# composite_router_draft_1.net
KiCad netlist of a schematic drawn in EAGLE
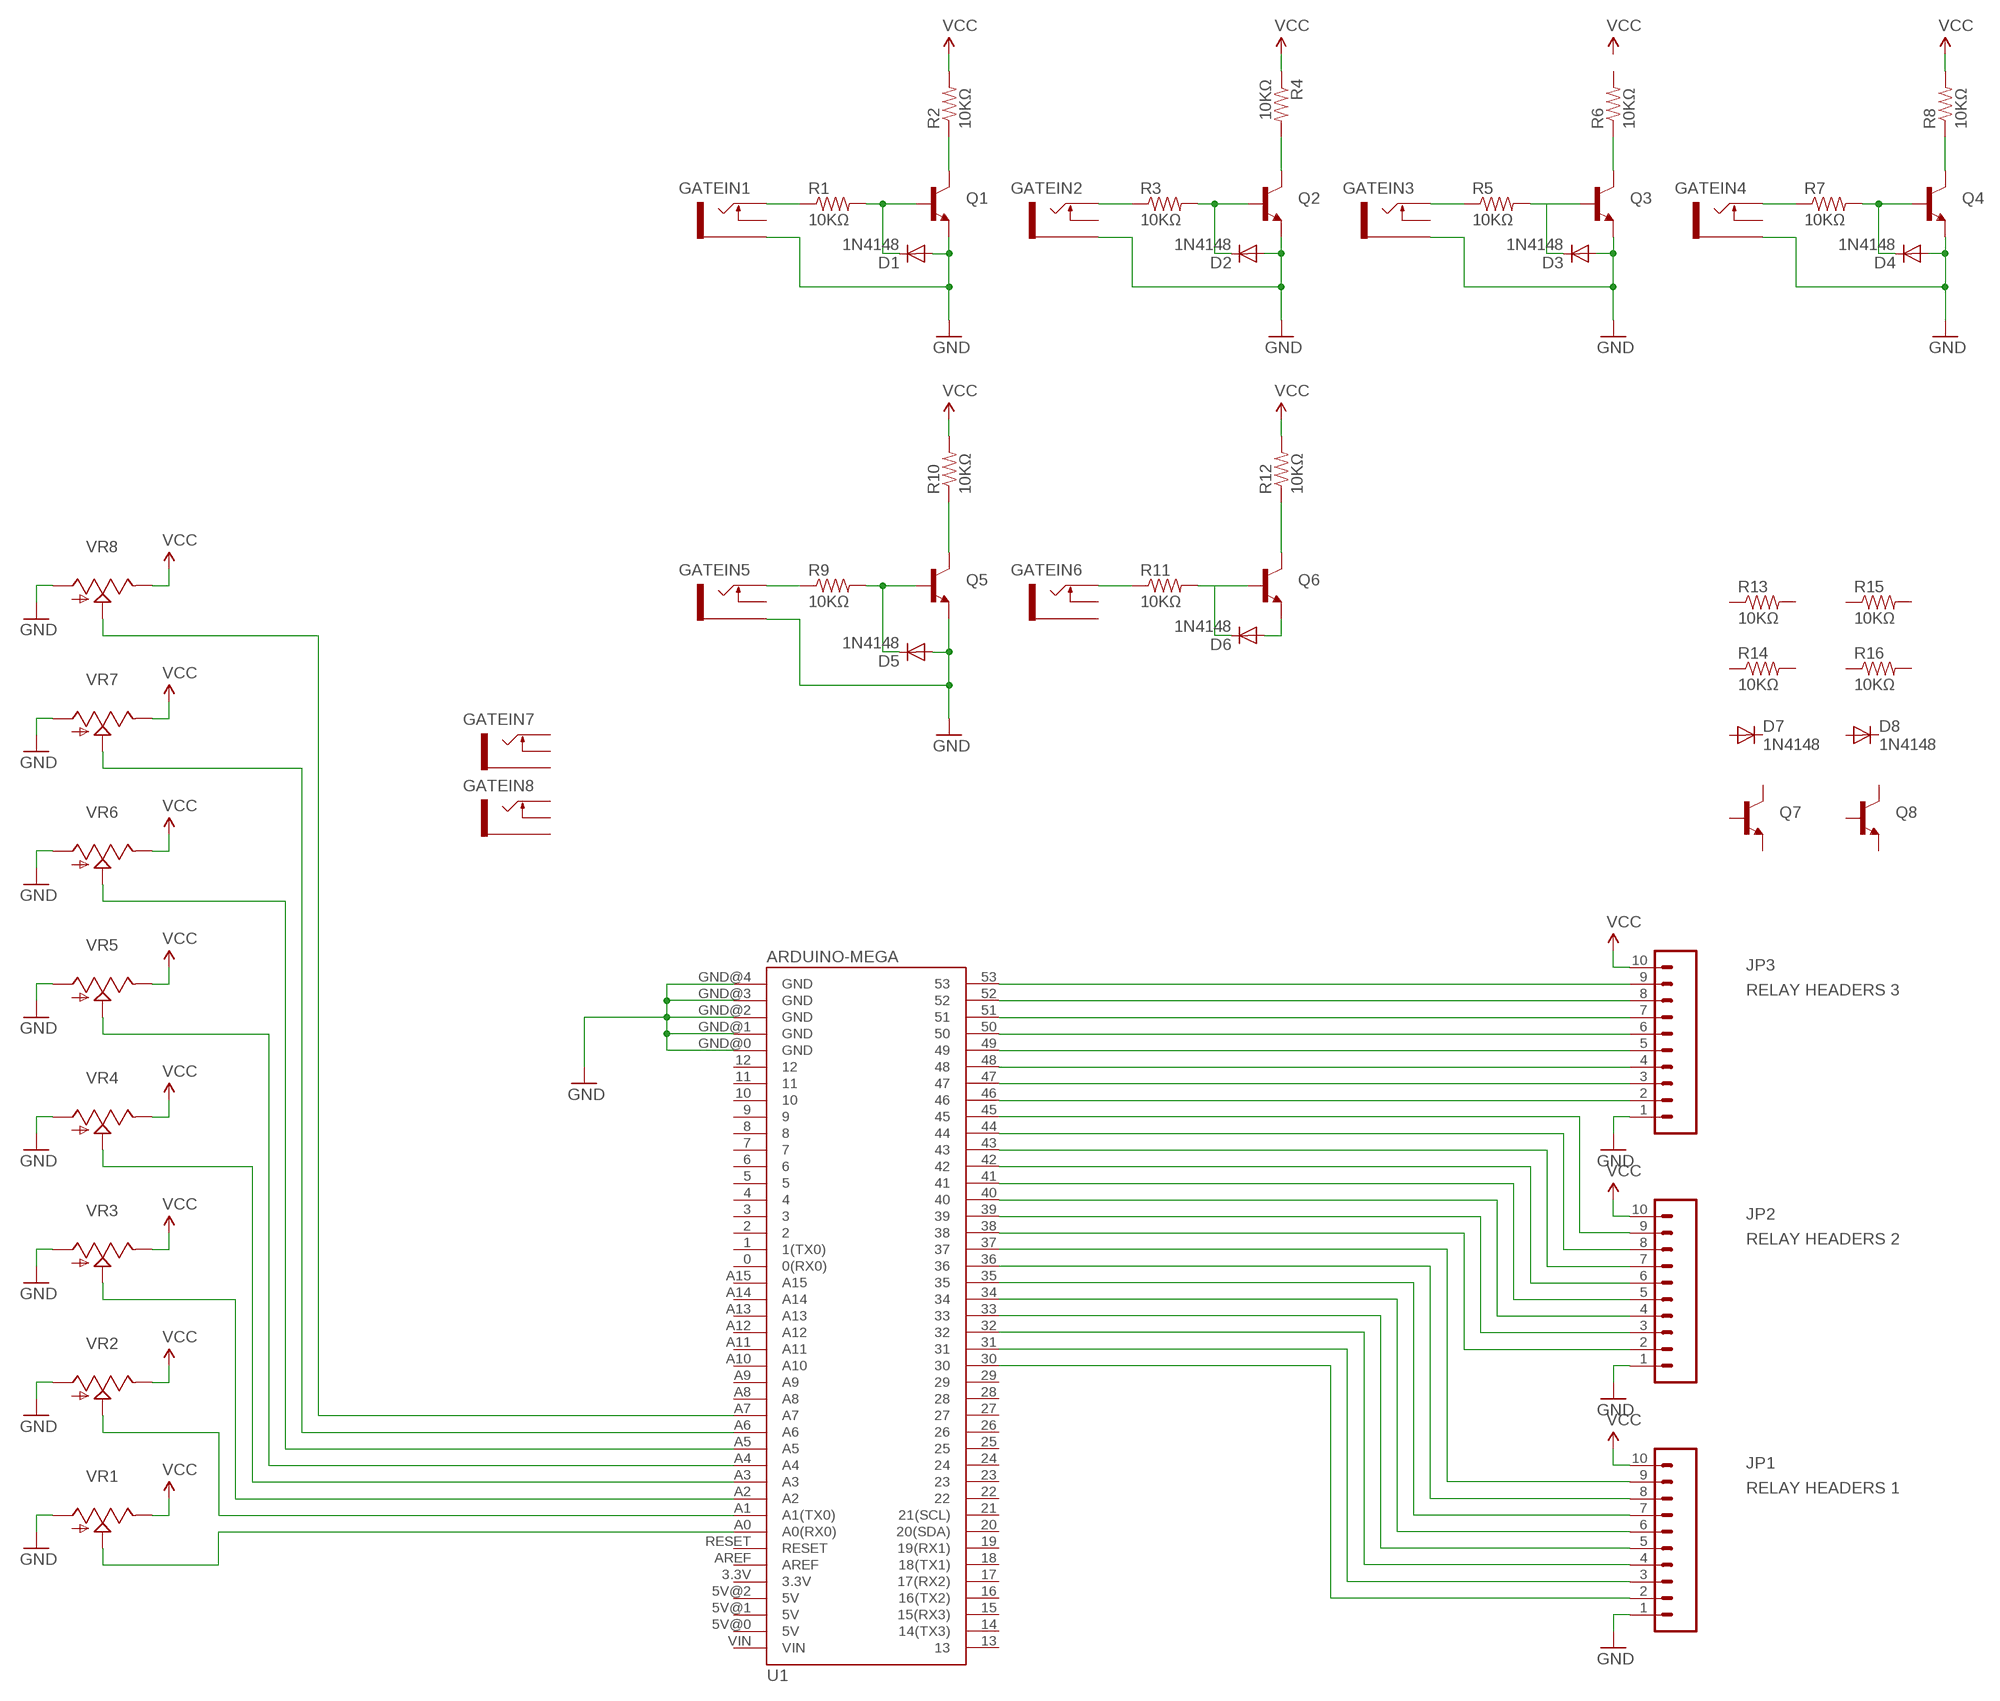
[diagram p0: schematic, sheet 1]

(export (version "E")
  (design (tool "Eeschema 10.0.6"))
  (components
    (comp (ref "D1")
      (value "1N4148")
      (footprint "eagle-import:DO35-7")
      (libsource (lib "eagle-import") (part "1N4148DO35-7"))
    )
    (comp (ref "D2")
      (value "1N4148")
      (footprint "eagle-import:DO35-7")
      (libsource (lib "eagle-import") (part "1N4148DO35-7"))
    )
    (comp (ref "D3")
      (value "1N4148")
      (footprint "eagle-import:DO35-7")
      (libsource (lib "eagle-import") (part "1N4148DO35-7"))
    )
    (comp (ref "D4")
      (value "1N4148")
      (footprint "eagle-import:DO35-7")
      (libsource (lib "eagle-import") (part "1N4148DO35-7"))
    )
    (comp (ref "D5")
      (value "1N4148")
      (footprint "eagle-import:DO35-7")
      (libsource (lib "eagle-import") (part "1N4148DO35-7"))
    )
    (comp (ref "D6")
      (value "1N4148")
      (footprint "eagle-import:DO35-7")
      (libsource (lib "eagle-import") (part "1N4148DO35-7"))
    )
    (comp (ref "D7")
      (value "1N4148")
      (footprint "eagle-import:DO35-7")
      (libsource (lib "eagle-import") (part "1N4148DO35-7"))
    )
    (comp (ref "D8")
      (value "1N4148")
      (footprint "eagle-import:DO35-7")
      (libsource (lib "eagle-import") (part "1N4148DO35-7"))
    )
    (comp (ref "GATEIN1")
      (value "THONKICONNNEW")
      (footprint "eagle-import:WQP-PJ301M-12_JACK")
      (libsource (lib "eagle-import") (part "THONKICONNNEW"))
    )
    (comp (ref "GATEIN2")
      (value "THONKICONNNEW")
      (footprint "eagle-import:WQP-PJ301M-12_JACK")
      (libsource (lib "eagle-import") (part "THONKICONNNEW"))
    )
    (comp (ref "GATEIN3")
      (value "THONKICONNNEW")
      (footprint "eagle-import:WQP-PJ301M-12_JACK")
      (libsource (lib "eagle-import") (part "THONKICONNNEW"))
    )
    (comp (ref "GATEIN4")
      (value "THONKICONNNEW")
      (footprint "eagle-import:WQP-PJ301M-12_JACK")
      (libsource (lib "eagle-import") (part "THONKICONNNEW"))
    )
    (comp (ref "GATEIN5")
      (value "THONKICONNNEW")
      (footprint "eagle-import:WQP-PJ301M-12_JACK")
      (libsource (lib "eagle-import") (part "THONKICONNNEW"))
    )
    (comp (ref "GATEIN6")
      (value "THONKICONNNEW")
      (footprint "eagle-import:WQP-PJ301M-12_JACK")
      (libsource (lib "eagle-import") (part "THONKICONNNEW"))
    )
    (comp (ref "GATEIN7")
      (value "THONKICONNNEW")
      (footprint "eagle-import:WQP-PJ301M-12_JACK")
      (libsource (lib "eagle-import") (part "THONKICONNNEW"))
    )
    (comp (ref "GATEIN8")
      (value "THONKICONNNEW")
      (footprint "eagle-import:WQP-PJ301M-12_JACK")
      (libsource (lib "eagle-import") (part "THONKICONNNEW"))
    )
    (comp (ref "JP1")
      (value "RELAY HEADERS 1")
      (footprint "eagle-import:1X10")
      (libsource (lib "eagle-import") (part "M10SILK_FEMALE_PTH"))
    )
    (comp (ref "JP2")
      (value "RELAY HEADERS 2")
      (footprint "eagle-import:1X10")
      (libsource (lib "eagle-import") (part "M10SILK_FEMALE_PTH"))
    )
    (comp (ref "JP3")
      (value "RELAY HEADERS 3")
      (footprint "eagle-import:1X10")
      (libsource (lib "eagle-import") (part "M10SILK_FEMALE_PTH"))
    )
    (comp (ref "Q1")
      (value "TRANSISTOR_NPN2N3904")
      (footprint "eagle-import:TO-92")
      (libsource (lib "eagle-import") (part "TRANSISTOR_NPN2N3904"))
    )
    (comp (ref "Q2")
      (value "TRANSISTOR_NPN2N3904")
      (footprint "eagle-import:TO-92")
      (libsource (lib "eagle-import") (part "TRANSISTOR_NPN2N3904"))
    )
    (comp (ref "Q3")
      (value "TRANSISTOR_NPN2N3904")
      (footprint "eagle-import:TO-92")
      (libsource (lib "eagle-import") (part "TRANSISTOR_NPN2N3904"))
    )
    (comp (ref "Q4")
      (value "TRANSISTOR_NPN2N3904")
      (footprint "eagle-import:TO-92")
      (libsource (lib "eagle-import") (part "TRANSISTOR_NPN2N3904"))
    )
    (comp (ref "Q5")
      (value "TRANSISTOR_NPN2N3904")
      (footprint "eagle-import:TO-92")
      (libsource (lib "eagle-import") (part "TRANSISTOR_NPN2N3904"))
    )
    (comp (ref "Q6")
      (value "TRANSISTOR_NPN2N3904")
      (footprint "eagle-import:TO-92")
      (libsource (lib "eagle-import") (part "TRANSISTOR_NPN2N3904"))
    )
    (comp (ref "Q7")
      (value "TRANSISTOR_NPN2N3904")
      (footprint "eagle-import:TO-92")
      (libsource (lib "eagle-import") (part "TRANSISTOR_NPN2N3904"))
    )
    (comp (ref "Q8")
      (value "TRANSISTOR_NPN2N3904")
      (footprint "eagle-import:TO-92")
      (libsource (lib "eagle-import") (part "TRANSISTOR_NPN2N3904"))
    )
    (comp (ref "R1")
      (value "10KΩ")
      (footprint "eagle-import:AXIAL-0.4")
      (libsource (lib "eagle-import") (part "RESISTORPTH-1/4W"))
    )
    (comp (ref "R2")
      (value "10KΩ")
      (footprint "eagle-import:AXIAL-0.4")
      (libsource (lib "eagle-import") (part "RESISTORPTH-1/4W"))
    )
    (comp (ref "R3")
      (value "10KΩ")
      (footprint "eagle-import:AXIAL-0.4")
      (libsource (lib "eagle-import") (part "RESISTORPTH-1/4W"))
    )
    (comp (ref "R4")
      (value "10KΩ")
      (footprint "eagle-import:AXIAL-0.4")
      (libsource (lib "eagle-import") (part "RESISTORPTH-1/4W"))
    )
    (comp (ref "R5")
      (value "10KΩ")
      (footprint "eagle-import:AXIAL-0.4")
      (libsource (lib "eagle-import") (part "RESISTORPTH-1/4W"))
    )
    (comp (ref "R6")
      (value "10KΩ")
      (footprint "eagle-import:AXIAL-0.4")
      (libsource (lib "eagle-import") (part "RESISTORPTH-1/4W"))
    )
    (comp (ref "R7")
      (value "10KΩ")
      (footprint "eagle-import:AXIAL-0.4")
      (libsource (lib "eagle-import") (part "RESISTORPTH-1/4W"))
    )
    (comp (ref "R8")
      (value "10KΩ")
      (footprint "eagle-import:AXIAL-0.4")
      (libsource (lib "eagle-import") (part "RESISTORPTH-1/4W"))
    )
    (comp (ref "R9")
      (value "10KΩ")
      (footprint "eagle-import:AXIAL-0.4")
      (libsource (lib "eagle-import") (part "RESISTORPTH-1/4W"))
    )
    (comp (ref "R10")
      (value "10KΩ")
      (footprint "eagle-import:AXIAL-0.4")
      (libsource (lib "eagle-import") (part "RESISTORPTH-1/4W"))
    )
    (comp (ref "R11")
      (value "10KΩ")
      (footprint "eagle-import:AXIAL-0.4")
      (libsource (lib "eagle-import") (part "RESISTORPTH-1/4W"))
    )
    (comp (ref "R12")
      (value "10KΩ")
      (footprint "eagle-import:AXIAL-0.4")
      (libsource (lib "eagle-import") (part "RESISTORPTH-1/4W"))
    )
    (comp (ref "R13")
      (value "10KΩ")
      (footprint "eagle-import:AXIAL-0.4")
      (libsource (lib "eagle-import") (part "RESISTORPTH-1/4W"))
    )
    (comp (ref "R14")
      (value "10KΩ")
      (footprint "eagle-import:AXIAL-0.4")
      (libsource (lib "eagle-import") (part "RESISTORPTH-1/4W"))
    )
    (comp (ref "R15")
      (value "10KΩ")
      (footprint "eagle-import:AXIAL-0.4")
      (libsource (lib "eagle-import") (part "RESISTORPTH-1/4W"))
    )
    (comp (ref "R16")
      (value "10KΩ")
      (footprint "eagle-import:AXIAL-0.4")
      (libsource (lib "eagle-import") (part "RESISTORPTH-1/4W"))
    )
    (comp (ref "U1")
      (value "ARDUINO-MEGA")
      (footprint "eagle-import:ARDUINO_MEGA")
      (libsource (lib "eagle-import") (part "ARDUINO-MEGAFULL"))
    )
    (comp (ref "VR1")
      (value "9MM_SNAP-IN_POT_")
      (footprint "eagle-import:9MM_SNAP-IN_POT")
      (libsource (lib "eagle-import") (part "9MM_SNAP-IN_POT_"))
    )
    (comp (ref "VR2")
      (value "9MM_SNAP-IN_POT_")
      (footprint "eagle-import:9MM_SNAP-IN_POT")
      (libsource (lib "eagle-import") (part "9MM_SNAP-IN_POT_"))
    )
    (comp (ref "VR3")
      (value "9MM_SNAP-IN_POT_")
      (footprint "eagle-import:9MM_SNAP-IN_POT")
      (libsource (lib "eagle-import") (part "9MM_SNAP-IN_POT_"))
    )
    (comp (ref "VR4")
      (value "9MM_SNAP-IN_POT_")
      (footprint "eagle-import:9MM_SNAP-IN_POT")
      (libsource (lib "eagle-import") (part "9MM_SNAP-IN_POT_"))
    )
    (comp (ref "VR5")
      (value "9MM_SNAP-IN_POT_")
      (footprint "eagle-import:9MM_SNAP-IN_POT")
      (libsource (lib "eagle-import") (part "9MM_SNAP-IN_POT_"))
    )
    (comp (ref "VR6")
      (value "9MM_SNAP-IN_POT_")
      (footprint "eagle-import:9MM_SNAP-IN_POT")
      (libsource (lib "eagle-import") (part "9MM_SNAP-IN_POT_"))
    )
    (comp (ref "VR7")
      (value "9MM_SNAP-IN_POT_")
      (footprint "eagle-import:9MM_SNAP-IN_POT")
      (libsource (lib "eagle-import") (part "9MM_SNAP-IN_POT_"))
    )
    (comp (ref "VR8")
      (value "9MM_SNAP-IN_POT_")
      (footprint "eagle-import:9MM_SNAP-IN_POT")
      (libsource (lib "eagle-import") (part "9MM_SNAP-IN_POT_"))
    )
  )
  (nets
    (net (code "1") (name "GND") (class "Default")
      (node (ref "D1") (pin "A") (pinfunction "A_A") (pintype "passive"))
      (node (ref "D2") (pin "A") (pinfunction "A_A") (pintype "passive"))
      (node (ref "D3") (pin "A") (pinfunction "A_A") (pintype "passive"))
      (node (ref "D4") (pin "A") (pinfunction "A_A") (pintype "passive"))
      (node (ref "D5") (pin "A") (pinfunction "A_A") (pintype "passive"))
      (node (ref "GATEIN1") (pin "P$3_SLEEVE") (pinfunction "SLEEVE_P$3_SLEEVE") (pintype "passive"))
      (node (ref "GATEIN2") (pin "P$3_SLEEVE") (pinfunction "SLEEVE_P$3_SLEEVE") (pintype "passive"))
      (node (ref "GATEIN3") (pin "P$3_SLEEVE") (pinfunction "SLEEVE_P$3_SLEEVE") (pintype "passive"))
      (node (ref "GATEIN4") (pin "P$3_SLEEVE") (pinfunction "SLEEVE_P$3_SLEEVE") (pintype "passive"))
      (node (ref "GATEIN5") (pin "P$3_SLEEVE") (pinfunction "SLEEVE_P$3_SLEEVE") (pintype "passive"))
      (node (ref "JP1") (pin "1") (pinfunction "1_1") (pintype "passive"))
      (node (ref "JP2") (pin "1") (pinfunction "1_1") (pintype "passive"))
      (node (ref "JP3") (pin "1") (pinfunction "1_1") (pintype "passive"))
      (node (ref "Q1") (pin "1") (pinfunction "E_1") (pintype "passive"))
      (node (ref "Q2") (pin "1") (pinfunction "E_1") (pintype "passive"))
      (node (ref "Q3") (pin "1") (pinfunction "E_1") (pintype "passive"))
      (node (ref "Q4") (pin "1") (pinfunction "E_1") (pintype "passive"))
      (node (ref "Q5") (pin "1") (pinfunction "E_1") (pintype "passive"))
      (node (ref "U1") (pin "GND@0") (pinfunction "GND_GND@0") (pintype "bidirectional"))
      (node (ref "U1") (pin "GND@1") (pinfunction "GND_GND@1") (pintype "bidirectional"))
      (node (ref "U1") (pin "GND@2") (pinfunction "GND_GND@2") (pintype "bidirectional"))
      (node (ref "U1") (pin "GND@3") (pinfunction "GND_GND@3") (pintype "bidirectional"))
      (node (ref "U1") (pin "GND@4") (pinfunction "GND_GND@4") (pintype "bidirectional"))
      (node (ref "VR1") (pin "1") (pinfunction "A_1") (pintype "passive"))
      (node (ref "VR2") (pin "1") (pinfunction "A_1") (pintype "passive"))
      (node (ref "VR3") (pin "1") (pinfunction "A_1") (pintype "passive"))
      (node (ref "VR4") (pin "1") (pinfunction "A_1") (pintype "passive"))
      (node (ref "VR5") (pin "1") (pinfunction "A_1") (pintype "passive"))
      (node (ref "VR6") (pin "1") (pinfunction "A_1") (pintype "passive"))
      (node (ref "VR7") (pin "1") (pinfunction "A_1") (pintype "passive"))
      (node (ref "VR8") (pin "1") (pinfunction "A_1") (pintype "passive"))
    )
    (net (code "2") (name "Net-(GATEIN1-TIP)") (class "Default")
      (node (ref "GATEIN1") (pin "P$1_TIP") (pinfunction "TIP_P$1_TIP") (pintype "passive"))
      (node (ref "R1") (pin "P$1") (pinfunction "1_P$1") (pintype "passive"))
    )
    (net (code "3") (name "Net-(GATEIN2-TIP)") (class "Default")
      (node (ref "GATEIN2") (pin "P$1_TIP") (pinfunction "TIP_P$1_TIP") (pintype "passive"))
      (node (ref "R3") (pin "P$1") (pinfunction "1_P$1") (pintype "passive"))
    )
    (net (code "4") (name "Net-(GATEIN3-TIP)") (class "Default")
      (node (ref "GATEIN3") (pin "P$1_TIP") (pinfunction "TIP_P$1_TIP") (pintype "passive"))
      (node (ref "R5") (pin "P$1") (pinfunction "1_P$1") (pintype "passive"))
    )
    (net (code "5") (name "Net-(GATEIN4-TIP)") (class "Default")
      (node (ref "GATEIN4") (pin "P$1_TIP") (pinfunction "TIP_P$1_TIP") (pintype "passive"))
      (node (ref "R7") (pin "P$1") (pinfunction "1_P$1") (pintype "passive"))
    )
    (net (code "6") (name "Net-(GATEIN5-TIP)") (class "Default")
      (node (ref "GATEIN5") (pin "P$1_TIP") (pinfunction "TIP_P$1_TIP") (pintype "passive"))
      (node (ref "R9") (pin "P$1") (pinfunction "1_P$1") (pintype "passive"))
    )
    (net (code "7") (name "Net-(GATEIN6-TIP)") (class "Default")
      (node (ref "GATEIN6") (pin "P$1_TIP") (pinfunction "TIP_P$1_TIP") (pintype "passive"))
      (node (ref "R11") (pin "P$1") (pinfunction "1_P$1") (pintype "passive"))
    )
    (net (code "8") (name "Net-(JP1-Pad2)") (class "Default")
      (node (ref "JP1") (pin "2") (pinfunction "2_2") (pintype "passive"))
      (node (ref "U1") (pin "30") (pinfunction "30_30") (pintype "bidirectional"))
    )
    (net (code "9") (name "Net-(JP1-Pad3)") (class "Default")
      (node (ref "JP1") (pin "3") (pinfunction "3_3") (pintype "passive"))
      (node (ref "U1") (pin "31") (pinfunction "31_31") (pintype "bidirectional"))
    )
    (net (code "10") (name "Net-(JP1-Pad4)") (class "Default")
      (node (ref "JP1") (pin "4") (pinfunction "4_4") (pintype "passive"))
      (node (ref "U1") (pin "32") (pinfunction "32_32") (pintype "bidirectional"))
    )
    (net (code "11") (name "Net-(JP1-Pad5)") (class "Default")
      (node (ref "JP1") (pin "5") (pinfunction "5_5") (pintype "passive"))
      (node (ref "U1") (pin "33") (pinfunction "33_33") (pintype "bidirectional"))
    )
    (net (code "12") (name "Net-(JP1-Pad6)") (class "Default")
      (node (ref "JP1") (pin "6") (pinfunction "6_6") (pintype "passive"))
      (node (ref "U1") (pin "34") (pinfunction "34_34") (pintype "bidirectional"))
    )
    (net (code "13") (name "Net-(JP1-Pad7)") (class "Default")
      (node (ref "JP1") (pin "7") (pinfunction "7_7") (pintype "passive"))
      (node (ref "U1") (pin "35") (pinfunction "35_35") (pintype "bidirectional"))
    )
    (net (code "14") (name "Net-(JP1-Pad8)") (class "Default")
      (node (ref "JP1") (pin "8") (pinfunction "8_8") (pintype "passive"))
      (node (ref "U1") (pin "36") (pinfunction "36_36") (pintype "bidirectional"))
    )
    (net (code "15") (name "Net-(JP1-Pad9)") (class "Default")
      (node (ref "JP1") (pin "9") (pinfunction "9_9") (pintype "passive"))
      (node (ref "U1") (pin "37") (pinfunction "37_37") (pintype "bidirectional"))
    )
    (net (code "16") (name "Net-(JP2-Pad2)") (class "Default")
      (node (ref "JP2") (pin "2") (pinfunction "2_2") (pintype "passive"))
      (node (ref "U1") (pin "38") (pinfunction "38_38") (pintype "bidirectional"))
    )
    (net (code "17") (name "Net-(JP2-Pad3)") (class "Default")
      (node (ref "JP2") (pin "3") (pinfunction "3_3") (pintype "passive"))
      (node (ref "U1") (pin "39") (pinfunction "39_39") (pintype "bidirectional"))
    )
    (net (code "18") (name "Net-(JP2-Pad4)") (class "Default")
      (node (ref "JP2") (pin "4") (pinfunction "4_4") (pintype "passive"))
      (node (ref "U1") (pin "40") (pinfunction "40_40") (pintype "bidirectional"))
    )
    (net (code "19") (name "Net-(JP2-Pad5)") (class "Default")
      (node (ref "JP2") (pin "5") (pinfunction "5_5") (pintype "passive"))
      (node (ref "U1") (pin "41") (pinfunction "41_41") (pintype "bidirectional"))
    )
    (net (code "20") (name "Net-(JP2-Pad6)") (class "Default")
      (node (ref "JP2") (pin "6") (pinfunction "6_6") (pintype "passive"))
      (node (ref "U1") (pin "42") (pinfunction "42_42") (pintype "bidirectional"))
    )
    (net (code "21") (name "Net-(JP2-Pad7)") (class "Default")
      (node (ref "JP2") (pin "7") (pinfunction "7_7") (pintype "passive"))
      (node (ref "U1") (pin "43") (pinfunction "43_43") (pintype "bidirectional"))
    )
    (net (code "22") (name "Net-(JP2-Pad8)") (class "Default")
      (node (ref "JP2") (pin "8") (pinfunction "8_8") (pintype "passive"))
      (node (ref "U1") (pin "44") (pinfunction "44_44") (pintype "bidirectional"))
    )
    (net (code "23") (name "Net-(JP2-Pad9)") (class "Default")
      (node (ref "JP2") (pin "9") (pinfunction "9_9") (pintype "passive"))
      (node (ref "U1") (pin "45") (pinfunction "45_45") (pintype "bidirectional"))
    )
    (net (code "24") (name "Net-(JP3-Pad2)") (class "Default")
      (node (ref "JP3") (pin "2") (pinfunction "2_2") (pintype "passive"))
      (node (ref "U1") (pin "46") (pinfunction "46_46") (pintype "bidirectional"))
    )
    (net (code "25") (name "Net-(JP3-Pad3)") (class "Default")
      (node (ref "JP3") (pin "3") (pinfunction "3_3") (pintype "passive"))
      (node (ref "U1") (pin "47") (pinfunction "47_47") (pintype "bidirectional"))
    )
    (net (code "26") (name "Net-(JP3-Pad4)") (class "Default")
      (node (ref "JP3") (pin "4") (pinfunction "4_4") (pintype "passive"))
      (node (ref "U1") (pin "48") (pinfunction "48_48") (pintype "bidirectional"))
    )
    (net (code "27") (name "Net-(JP3-Pad5)") (class "Default")
      (node (ref "JP3") (pin "5") (pinfunction "5_5") (pintype "passive"))
      (node (ref "U1") (pin "49") (pinfunction "49_49") (pintype "bidirectional"))
    )
    (net (code "28") (name "Net-(JP3-Pad6)") (class "Default")
      (node (ref "JP3") (pin "6") (pinfunction "6_6") (pintype "passive"))
      (node (ref "U1") (pin "50") (pinfunction "50_50") (pintype "bidirectional"))
    )
    (net (code "29") (name "Net-(JP3-Pad7)") (class "Default")
      (node (ref "JP3") (pin "7") (pinfunction "7_7") (pintype "passive"))
      (node (ref "U1") (pin "51") (pinfunction "51_51") (pintype "bidirectional"))
    )
    (net (code "30") (name "Net-(JP3-Pad8)") (class "Default")
      (node (ref "JP3") (pin "8") (pinfunction "8_8") (pintype "passive"))
      (node (ref "U1") (pin "52") (pinfunction "52_52") (pintype "bidirectional"))
    )
    (net (code "31") (name "Net-(JP3-Pad9)") (class "Default")
      (node (ref "JP3") (pin "9") (pinfunction "9_9") (pintype "passive"))
      (node (ref "U1") (pin "53") (pinfunction "53_53") (pintype "bidirectional"))
    )
    (net (code "32") (name "Net-(Q1-B)") (class "Default")
      (node (ref "D1") (pin "C") (pinfunction "C_C") (pintype "passive"))
      (node (ref "Q1") (pin "2") (pinfunction "B_2") (pintype "passive"))
      (node (ref "R1") (pin "P$2") (pinfunction "2_P$2") (pintype "passive"))
    )
    (net (code "33") (name "Net-(Q1-C)") (class "Default")
      (node (ref "Q1") (pin "3") (pinfunction "C_3") (pintype "passive"))
      (node (ref "R2") (pin "P$1") (pinfunction "1_P$1") (pintype "passive"))
    )
    (net (code "34") (name "Net-(Q2-B)") (class "Default")
      (node (ref "D2") (pin "C") (pinfunction "C_C") (pintype "passive"))
      (node (ref "Q2") (pin "2") (pinfunction "B_2") (pintype "passive"))
      (node (ref "R3") (pin "P$2") (pinfunction "2_P$2") (pintype "passive"))
    )
    (net (code "35") (name "Net-(Q2-C)") (class "Default")
      (node (ref "Q2") (pin "3") (pinfunction "C_3") (pintype "passive"))
      (node (ref "R4") (pin "P$2") (pinfunction "2_P$2") (pintype "passive"))
    )
    (net (code "36") (name "Net-(Q3-B)") (class "Default")
      (node (ref "D3") (pin "C") (pinfunction "C_C") (pintype "passive"))
      (node (ref "Q3") (pin "2") (pinfunction "B_2") (pintype "passive"))
      (node (ref "R5") (pin "P$2") (pinfunction "2_P$2") (pintype "passive"))
    )
    (net (code "37") (name "Net-(Q3-C)") (class "Default")
      (node (ref "Q3") (pin "3") (pinfunction "C_3") (pintype "passive"))
      (node (ref "R6") (pin "P$1") (pinfunction "1_P$1") (pintype "passive"))
    )
    (net (code "38") (name "Net-(Q4-B)") (class "Default")
      (node (ref "D4") (pin "C") (pinfunction "C_C") (pintype "passive"))
      (node (ref "Q4") (pin "2") (pinfunction "B_2") (pintype "passive"))
      (node (ref "R7") (pin "P$2") (pinfunction "2_P$2") (pintype "passive"))
    )
    (net (code "39") (name "Net-(Q4-C)") (class "Default")
      (node (ref "Q4") (pin "3") (pinfunction "C_3") (pintype "passive"))
      (node (ref "R8") (pin "P$1") (pinfunction "1_P$1") (pintype "passive"))
    )
    (net (code "40") (name "Net-(Q5-B)") (class "Default")
      (node (ref "D5") (pin "C") (pinfunction "C_C") (pintype "passive"))
      (node (ref "Q5") (pin "2") (pinfunction "B_2") (pintype "passive"))
      (node (ref "R9") (pin "P$2") (pinfunction "2_P$2") (pintype "passive"))
    )
    (net (code "41") (name "Net-(Q5-C)") (class "Default")
      (node (ref "Q5") (pin "3") (pinfunction "C_3") (pintype "passive"))
      (node (ref "R10") (pin "P$1") (pinfunction "1_P$1") (pintype "passive"))
    )
    (net (code "42") (name "Net-(Q6-B)") (class "Default")
      (node (ref "D6") (pin "C") (pinfunction "C_C") (pintype "passive"))
      (node (ref "Q6") (pin "2") (pinfunction "B_2") (pintype "passive"))
      (node (ref "R11") (pin "P$2") (pinfunction "2_P$2") (pintype "passive"))
    )
    (net (code "43") (name "Net-(Q6-C)") (class "Default")
      (node (ref "Q6") (pin "3") (pinfunction "C_3") (pintype "passive"))
      (node (ref "R12") (pin "P$1") (pinfunction "1_P$1") (pintype "passive"))
    )
    (net (code "44") (name "Net-(Q6-E)") (class "Default")
      (node (ref "D6") (pin "A") (pinfunction "A_A") (pintype "passive"))
      (node (ref "Q6") (pin "1") (pinfunction "E_1") (pintype "passive"))
    )
    (net (code "45") (name "Net-(U1-A0(RX0))") (class "Default")
      (node (ref "U1") (pin "A0") (pinfunction "A0(RX0)_A0") (pintype "bidirectional"))
      (node (ref "VR1") (pin "2") (pinfunction "S_2") (pintype "passive"))
    )
    (net (code "46") (name "Net-(U1-A1(TX0))") (class "Default")
      (node (ref "U1") (pin "A1") (pinfunction "A1(TX0)_A1") (pintype "bidirectional"))
      (node (ref "VR2") (pin "2") (pinfunction "S_2") (pintype "passive"))
    )
    (net (code "47") (name "Net-(VR3-S)") (class "Default")
      (node (ref "U1") (pin "A2") (pinfunction "A2_A2") (pintype "bidirectional"))
      (node (ref "VR3") (pin "2") (pinfunction "S_2") (pintype "passive"))
    )
    (net (code "48") (name "Net-(VR4-S)") (class "Default")
      (node (ref "U1") (pin "A3") (pinfunction "A3_A3") (pintype "bidirectional"))
      (node (ref "VR4") (pin "2") (pinfunction "S_2") (pintype "passive"))
    )
    (net (code "49") (name "Net-(VR5-S)") (class "Default")
      (node (ref "U1") (pin "A4") (pinfunction "A4_A4") (pintype "bidirectional"))
      (node (ref "VR5") (pin "2") (pinfunction "S_2") (pintype "passive"))
    )
    (net (code "50") (name "Net-(VR6-S)") (class "Default")
      (node (ref "U1") (pin "A5") (pinfunction "A5_A5") (pintype "bidirectional"))
      (node (ref "VR6") (pin "2") (pinfunction "S_2") (pintype "passive"))
    )
    (net (code "51") (name "Net-(VR7-S)") (class "Default")
      (node (ref "U1") (pin "A6") (pinfunction "A6_A6") (pintype "bidirectional"))
      (node (ref "VR7") (pin "2") (pinfunction "S_2") (pintype "passive"))
    )
    (net (code "52") (name "Net-(VR8-S)") (class "Default")
      (node (ref "U1") (pin "A7") (pinfunction "A7_A7") (pintype "bidirectional"))
      (node (ref "VR8") (pin "2") (pinfunction "S_2") (pintype "passive"))
    )
    (net (code "53") (name "VCC") (class "Default")
      (node (ref "JP1") (pin "10") (pinfunction "10_10") (pintype "passive"))
      (node (ref "JP2") (pin "10") (pinfunction "10_10") (pintype "passive"))
      (node (ref "JP3") (pin "10") (pinfunction "10_10") (pintype "passive"))
      (node (ref "R10") (pin "P$2") (pinfunction "2_P$2") (pintype "passive"))
      (node (ref "R12") (pin "P$2") (pinfunction "2_P$2") (pintype "passive"))
      (node (ref "R2") (pin "P$2") (pinfunction "2_P$2") (pintype "passive"))
      (node (ref "R4") (pin "P$1") (pinfunction "1_P$1") (pintype "passive"))
      (node (ref "R8") (pin "P$2") (pinfunction "2_P$2") (pintype "passive"))
      (node (ref "VR1") (pin "3") (pinfunction "E_3") (pintype "passive"))
      (node (ref "VR2") (pin "3") (pinfunction "E_3") (pintype "passive"))
      (node (ref "VR3") (pin "3") (pinfunction "E_3") (pintype "passive"))
      (node (ref "VR4") (pin "3") (pinfunction "E_3") (pintype "passive"))
      (node (ref "VR5") (pin "3") (pinfunction "E_3") (pintype "passive"))
      (node (ref "VR6") (pin "3") (pinfunction "E_3") (pintype "passive"))
      (node (ref "VR7") (pin "3") (pinfunction "E_3") (pintype "passive"))
      (node (ref "VR8") (pin "3") (pinfunction "E_3") (pintype "passive"))
    )
    (net (code "54") (name "unconnected-(D7-PadA)") (class "Default")
      (node (ref "D7") (pin "A") (pinfunction "A_A") (pintype "passive"))
    )
    (net (code "55") (name "unconnected-(D7-PadC)") (class "Default")
      (node (ref "D7") (pin "C") (pinfunction "C_C") (pintype "passive"))
    )
    (net (code "56") (name "unconnected-(D8-PadA)") (class "Default")
      (node (ref "D8") (pin "A") (pinfunction "A_A") (pintype "passive"))
    )
    (net (code "57") (name "unconnected-(D8-PadC)") (class "Default")
      (node (ref "D8") (pin "C") (pinfunction "C_C") (pintype "passive"))
    )
    (net (code "58") (name "unconnected-(GATEIN1-SWITCH-PadP$2_SWITCH)") (class "Default")
      (node (ref "GATEIN1") (pin "P$2_SWITCH") (pinfunction "SWITCH_P$2_SWITCH") (pintype "passive"))
    )
    (net (code "59") (name "unconnected-(GATEIN2-SWITCH-PadP$2_SWITCH)") (class "Default")
      (node (ref "GATEIN2") (pin "P$2_SWITCH") (pinfunction "SWITCH_P$2_SWITCH") (pintype "passive"))
    )
    (net (code "60") (name "unconnected-(GATEIN3-SWITCH-PadP$2_SWITCH)") (class "Default")
      (node (ref "GATEIN3") (pin "P$2_SWITCH") (pinfunction "SWITCH_P$2_SWITCH") (pintype "passive"))
    )
    (net (code "61") (name "unconnected-(GATEIN4-SWITCH-PadP$2_SWITCH)") (class "Default")
      (node (ref "GATEIN4") (pin "P$2_SWITCH") (pinfunction "SWITCH_P$2_SWITCH") (pintype "passive"))
    )
    (net (code "62") (name "unconnected-(GATEIN5-SWITCH-PadP$2_SWITCH)") (class "Default")
      (node (ref "GATEIN5") (pin "P$2_SWITCH") (pinfunction "SWITCH_P$2_SWITCH") (pintype "passive"))
    )
    (net (code "63") (name "unconnected-(GATEIN6-SLEEVE-PadP$3_SLEEVE)") (class "Default")
      (node (ref "GATEIN6") (pin "P$3_SLEEVE") (pinfunction "SLEEVE_P$3_SLEEVE") (pintype "passive"))
    )
    (net (code "64") (name "unconnected-(GATEIN6-SWITCH-PadP$2_SWITCH)") (class "Default")
      (node (ref "GATEIN6") (pin "P$2_SWITCH") (pinfunction "SWITCH_P$2_SWITCH") (pintype "passive"))
    )
    (net (code "65") (name "unconnected-(GATEIN7-SLEEVE-PadP$3_SLEEVE)") (class "Default")
      (node (ref "GATEIN7") (pin "P$3_SLEEVE") (pinfunction "SLEEVE_P$3_SLEEVE") (pintype "passive"))
    )
    (net (code "66") (name "unconnected-(GATEIN7-SWITCH-PadP$2_SWITCH)") (class "Default")
      (node (ref "GATEIN7") (pin "P$2_SWITCH") (pinfunction "SWITCH_P$2_SWITCH") (pintype "passive"))
    )
    (net (code "67") (name "unconnected-(GATEIN7-TIP-PadP$1_TIP)") (class "Default")
      (node (ref "GATEIN7") (pin "P$1_TIP") (pinfunction "TIP_P$1_TIP") (pintype "passive"))
    )
    (net (code "68") (name "unconnected-(GATEIN8-SLEEVE-PadP$3_SLEEVE)") (class "Default")
      (node (ref "GATEIN8") (pin "P$3_SLEEVE") (pinfunction "SLEEVE_P$3_SLEEVE") (pintype "passive"))
    )
    (net (code "69") (name "unconnected-(GATEIN8-SWITCH-PadP$2_SWITCH)") (class "Default")
      (node (ref "GATEIN8") (pin "P$2_SWITCH") (pinfunction "SWITCH_P$2_SWITCH") (pintype "passive"))
    )
    (net (code "70") (name "unconnected-(GATEIN8-TIP-PadP$1_TIP)") (class "Default")
      (node (ref "GATEIN8") (pin "P$1_TIP") (pinfunction "TIP_P$1_TIP") (pintype "passive"))
    )
    (net (code "71") (name "unconnected-(Q7-B-Pad2)") (class "Default")
      (node (ref "Q7") (pin "2") (pinfunction "B_2") (pintype "passive"))
    )
    (net (code "72") (name "unconnected-(Q7-C-Pad3)") (class "Default")
      (node (ref "Q7") (pin "3") (pinfunction "C_3") (pintype "passive"))
    )
    (net (code "73") (name "unconnected-(Q7-E-Pad1)") (class "Default")
      (node (ref "Q7") (pin "1") (pinfunction "E_1") (pintype "passive"))
    )
    (net (code "74") (name "unconnected-(Q8-B-Pad2)") (class "Default")
      (node (ref "Q8") (pin "2") (pinfunction "B_2") (pintype "passive"))
    )
    (net (code "75") (name "unconnected-(Q8-C-Pad3)") (class "Default")
      (node (ref "Q8") (pin "3") (pinfunction "C_3") (pintype "passive"))
    )
    (net (code "76") (name "unconnected-(Q8-E-Pad1)") (class "Default")
      (node (ref "Q8") (pin "1") (pinfunction "E_1") (pintype "passive"))
    )
    (net (code "77") (name "unconnected-(R6-2-PadP$2)") (class "Default")
      (node (ref "R6") (pin "P$2") (pinfunction "2_P$2") (pintype "passive"))
    )
    (net (code "78") (name "unconnected-(R13-1-PadP$1)") (class "Default")
      (node (ref "R13") (pin "P$1") (pinfunction "1_P$1") (pintype "passive"))
    )
    (net (code "79") (name "unconnected-(R13-2-PadP$2)") (class "Default")
      (node (ref "R13") (pin "P$2") (pinfunction "2_P$2") (pintype "passive"))
    )
    (net (code "80") (name "unconnected-(R14-1-PadP$1)") (class "Default")
      (node (ref "R14") (pin "P$1") (pinfunction "1_P$1") (pintype "passive"))
    )
    (net (code "81") (name "unconnected-(R14-2-PadP$2)") (class "Default")
      (node (ref "R14") (pin "P$2") (pinfunction "2_P$2") (pintype "passive"))
    )
    (net (code "82") (name "unconnected-(R15-1-PadP$1)") (class "Default")
      (node (ref "R15") (pin "P$1") (pinfunction "1_P$1") (pintype "passive"))
    )
    (net (code "83") (name "unconnected-(R15-2-PadP$2)") (class "Default")
      (node (ref "R15") (pin "P$2") (pinfunction "2_P$2") (pintype "passive"))
    )
    (net (code "84") (name "unconnected-(R16-1-PadP$1)") (class "Default")
      (node (ref "R16") (pin "P$1") (pinfunction "1_P$1") (pintype "passive"))
    )
    (net (code "85") (name "unconnected-(R16-2-PadP$2)") (class "Default")
      (node (ref "R16") (pin "P$2") (pinfunction "2_P$2") (pintype "passive"))
    )
    (net (code "86") (name "unconnected-(U1-0(RX0)-Pad0)") (class "Default")
      (node (ref "U1") (pin "0") (pinfunction "0(RX0)_0") (pintype "bidirectional"))
    )
    (net (code "87") (name "unconnected-(U1-1(TX0)-Pad1)") (class "Default")
      (node (ref "U1") (pin "1") (pinfunction "1(TX0)_1") (pintype "bidirectional"))
    )
    (net (code "88") (name "unconnected-(U1-5V-Pad5V@0)") (class "Default")
      (node (ref "U1") (pin "5V@0") (pinfunction "5V_5V@0") (pintype "bidirectional"))
    )
    (net (code "89") (name "unconnected-(U1-5V-Pad5V@1)") (class "Default")
      (node (ref "U1") (pin "5V@1") (pinfunction "5V_5V@1") (pintype "bidirectional"))
    )
    (net (code "90") (name "unconnected-(U1-5V-Pad5V@2)") (class "Default")
      (node (ref "U1") (pin "5V@2") (pinfunction "5V_5V@2") (pintype "bidirectional"))
    )
    (net (code "91") (name "unconnected-(U1-14(TX3)-Pad14)") (class "Default")
      (node (ref "U1") (pin "14") (pinfunction "14(TX3)_14") (pintype "bidirectional"))
    )
    (net (code "92") (name "unconnected-(U1-15(RX3)-Pad15)") (class "Default")
      (node (ref "U1") (pin "15") (pinfunction "15(RX3)_15") (pintype "bidirectional"))
    )
    (net (code "93") (name "unconnected-(U1-16(TX2)-Pad16)") (class "Default")
      (node (ref "U1") (pin "16") (pinfunction "16(TX2)_16") (pintype "bidirectional"))
    )
    (net (code "94") (name "unconnected-(U1-17(RX2)-Pad17)") (class "Default")
      (node (ref "U1") (pin "17") (pinfunction "17(RX2)_17") (pintype "bidirectional"))
    )
    (net (code "95") (name "unconnected-(U1-18(TX1)-Pad18)") (class "Default")
      (node (ref "U1") (pin "18") (pinfunction "18(TX1)_18") (pintype "bidirectional"))
    )
    (net (code "96") (name "unconnected-(U1-19(RX1)-Pad19)") (class "Default")
      (node (ref "U1") (pin "19") (pinfunction "19(RX1)_19") (pintype "bidirectional"))
    )
    (net (code "97") (name "unconnected-(U1-20(SDA)-Pad20)") (class "Default")
      (node (ref "U1") (pin "20") (pinfunction "20(SDA)_20") (pintype "bidirectional"))
    )
    (net (code "98") (name "unconnected-(U1-21(SCL)-Pad21)") (class "Default")
      (node (ref "U1") (pin "21") (pinfunction "21(SCL)_21") (pintype "bidirectional"))
    )
    (net (code "99") (name "unconnected-(U1-Pad2)") (class "Default")
      (node (ref "U1") (pin "2") (pinfunction "2_2") (pintype "bidirectional"))
    )
    (net (code "100") (name "unconnected-(U1-Pad3)") (class "Default")
      (node (ref "U1") (pin "3") (pinfunction "3_3") (pintype "bidirectional"))
    )
    (net (code "101") (name "unconnected-(U1-Pad3.3V)") (class "Default")
      (node (ref "U1") (pin "3.3V") (pinfunction "3.3V_3.3V") (pintype "bidirectional"))
    )
    (net (code "102") (name "unconnected-(U1-Pad4)") (class "Default")
      (node (ref "U1") (pin "4") (pinfunction "4_4") (pintype "bidirectional"))
    )
    (net (code "103") (name "unconnected-(U1-Pad5)") (class "Default")
      (node (ref "U1") (pin "5") (pinfunction "5_5") (pintype "bidirectional"))
    )
    (net (code "104") (name "unconnected-(U1-Pad6)") (class "Default")
      (node (ref "U1") (pin "6") (pinfunction "6_6") (pintype "bidirectional"))
    )
    (net (code "105") (name "unconnected-(U1-Pad7)") (class "Default")
      (node (ref "U1") (pin "7") (pinfunction "7_7") (pintype "bidirectional"))
    )
    (net (code "106") (name "unconnected-(U1-Pad8)") (class "Default")
      (node (ref "U1") (pin "8") (pinfunction "8_8") (pintype "bidirectional"))
    )
    (net (code "107") (name "unconnected-(U1-Pad9)") (class "Default")
      (node (ref "U1") (pin "9") (pinfunction "9_9") (pintype "bidirectional"))
    )
    (net (code "108") (name "unconnected-(U1-Pad10)") (class "Default")
      (node (ref "U1") (pin "10") (pinfunction "10_10") (pintype "bidirectional"))
    )
    (net (code "109") (name "unconnected-(U1-Pad11)") (class "Default")
      (node (ref "U1") (pin "11") (pinfunction "11_11") (pintype "bidirectional"))
    )
    (net (code "110") (name "unconnected-(U1-Pad12)") (class "Default")
      (node (ref "U1") (pin "12") (pinfunction "12_12") (pintype "bidirectional"))
    )
    (net (code "111") (name "unconnected-(U1-Pad13)") (class "Default")
      (node (ref "U1") (pin "13") (pinfunction "13_13") (pintype "bidirectional"))
    )
    (net (code "112") (name "unconnected-(U1-Pad22)") (class "Default")
      (node (ref "U1") (pin "22") (pinfunction "22_22") (pintype "bidirectional"))
    )
    (net (code "113") (name "unconnected-(U1-Pad23)") (class "Default")
      (node (ref "U1") (pin "23") (pinfunction "23_23") (pintype "bidirectional"))
    )
    (net (code "114") (name "unconnected-(U1-Pad24)") (class "Default")
      (node (ref "U1") (pin "24") (pinfunction "24_24") (pintype "bidirectional"))
    )
    (net (code "115") (name "unconnected-(U1-Pad25)") (class "Default")
      (node (ref "U1") (pin "25") (pinfunction "25_25") (pintype "bidirectional"))
    )
    (net (code "116") (name "unconnected-(U1-Pad26)") (class "Default")
      (node (ref "U1") (pin "26") (pinfunction "26_26") (pintype "bidirectional"))
    )
    (net (code "117") (name "unconnected-(U1-Pad27)") (class "Default")
      (node (ref "U1") (pin "27") (pinfunction "27_27") (pintype "bidirectional"))
    )
    (net (code "118") (name "unconnected-(U1-Pad28)") (class "Default")
      (node (ref "U1") (pin "28") (pinfunction "28_28") (pintype "bidirectional"))
    )
    (net (code "119") (name "unconnected-(U1-Pad29)") (class "Default")
      (node (ref "U1") (pin "29") (pinfunction "29_29") (pintype "bidirectional"))
    )
    (net (code "120") (name "unconnected-(U1-PadA8)") (class "Default")
      (node (ref "U1") (pin "A8") (pinfunction "A8_A8") (pintype "bidirectional"))
    )
    (net (code "121") (name "unconnected-(U1-PadA9)") (class "Default")
      (node (ref "U1") (pin "A9") (pinfunction "A9_A9") (pintype "bidirectional"))
    )
    (net (code "122") (name "unconnected-(U1-PadA10)") (class "Default")
      (node (ref "U1") (pin "A10") (pinfunction "A10_A10") (pintype "bidirectional"))
    )
    (net (code "123") (name "unconnected-(U1-PadA11)") (class "Default")
      (node (ref "U1") (pin "A11") (pinfunction "A11_A11") (pintype "bidirectional"))
    )
    (net (code "124") (name "unconnected-(U1-PadA12)") (class "Default")
      (node (ref "U1") (pin "A12") (pinfunction "A12_A12") (pintype "bidirectional"))
    )
    (net (code "125") (name "unconnected-(U1-PadA13)") (class "Default")
      (node (ref "U1") (pin "A13") (pinfunction "A13_A13") (pintype "bidirectional"))
    )
    (net (code "126") (name "unconnected-(U1-PadA14)") (class "Default")
      (node (ref "U1") (pin "A14") (pinfunction "A14_A14") (pintype "bidirectional"))
    )
    (net (code "127") (name "unconnected-(U1-PadA15)") (class "Default")
      (node (ref "U1") (pin "A15") (pinfunction "A15_A15") (pintype "bidirectional"))
    )
    (net (code "128") (name "unconnected-(U1-PadAREF)") (class "Default")
      (node (ref "U1") (pin "AREF") (pinfunction "AREF_AREF") (pintype "bidirectional"))
    )
    (net (code "129") (name "unconnected-(U1-PadRESET)") (class "Default")
      (node (ref "U1") (pin "RESET") (pinfunction "RESET_RESET") (pintype "bidirectional"))
    )
    (net (code "130") (name "unconnected-(U1-PadVIN)") (class "Default")
      (node (ref "U1") (pin "VIN") (pinfunction "VIN_VIN") (pintype "bidirectional"))
    )
  )
)
